# Single_stage.net
KiCad netlist of a schematic drawn in Altium Designer
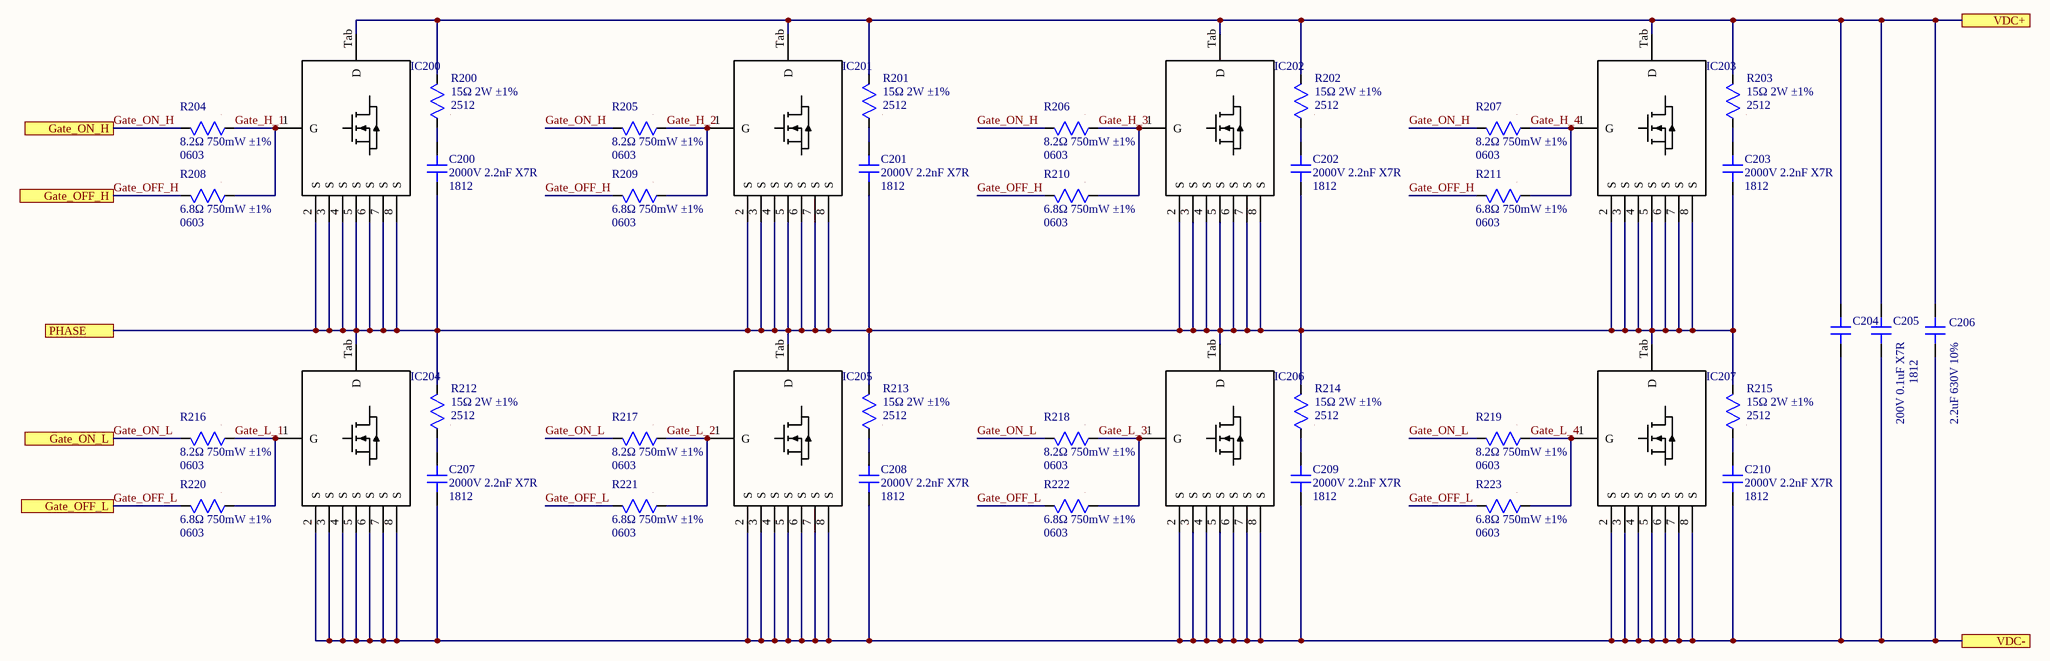
[diagram p0: Single_stage.SchDoc]

(export (version "E")
  (design (tool "Eeschema 10.0.6"))
  (components
    (comp (ref "C200")
      (value "2000V 2.2nF X7R")
      (footprint "CAP SMD 1812")
      (description "Condensadores de cerámica multicapa (MLCC- SMD/SMT) WCAP-CSMH 2000V 2200pF 1812 10%")
      (fields
        (field (name "PACKAGE") "1812")
        (field (name "MPN") "885342211007")
        (field (name "MANUFACTURER") "Wurth Elektronik")
      )
      (libsource (lib "eUSR_Database") (part "CAP non polarized"))
    )
    (comp (ref "C201")
      (value "2000V 2.2nF X7R")
      (footprint "CAP SMD 1812")
      (description "Condensadores de cerámica multicapa (MLCC- SMD/SMT) WCAP-CSMH 2000V 2200pF 1812 10%")
      (fields
        (field (name "PACKAGE") "1812")
        (field (name "MPN") "885342211007")
        (field (name "MANUFACTURER") "Wurth Elektronik")
      )
      (libsource (lib "eUSR_Database") (part "CAP non polarized"))
    )
    (comp (ref "C202")
      (value "2000V 2.2nF X7R")
      (footprint "CAP SMD 1812")
      (description "Condensadores de cerámica multicapa (MLCC- SMD/SMT) WCAP-CSMH 2000V 2200pF 1812 10%")
      (fields
        (field (name "PACKAGE") "1812")
        (field (name "MPN") "885342211007")
        (field (name "MANUFACTURER") "Wurth Elektronik")
      )
      (libsource (lib "eUSR_Database") (part "CAP non polarized"))
    )
    (comp (ref "C203")
      (value "2000V 2.2nF X7R")
      (footprint "CAP SMD 1812")
      (description "Condensadores de cerámica multicapa (MLCC- SMD/SMT) WCAP-CSMH 2000V 2200pF 1812 10%")
      (fields
        (field (name "PACKAGE") "1812")
        (field (name "MPN") "885342211007")
        (field (name "MANUFACTURER") "Wurth Elektronik")
      )
      (libsource (lib "eUSR_Database") (part "CAP non polarized"))
    )
    (comp (ref "C204")
      (value "CAP non polarized")
      (footprint "CAP SMD 1812")
      (description "Condensadores de cerámica multicapa (MLCC- SMD/SMT) WCAP-CSMH 200V 0.1uF 1812 10%")
      (fields (field (name "MPN") "885342211002") (field (name "MANUFACTURER") "Wurth Elektronik"))
      (libsource (lib "eUSR_Database") (part "CAP non polarized"))
    )
    (comp (ref "C205")
      (value "200V 0.1uF X7R")
      (footprint "CAP SMD 1812")
      (description "Condensadores de cerámica multicapa (MLCC- SMD/SMT) WCAP-CSMH 200V 0.1uF 1812 10%")
      (fields
        (field (name "PACKAGE") "1812")
        (field (name "MPN") "885342211002")
        (field (name "MANUFACTURER") "Wurth Elektronik")
      )
      (libsource (lib "eUSR_Database") (part "CAP non polarized"))
    )
    (comp (ref "C206")
      (value "2.2uF 630V 10%")
      (footprint "CAP_27.5Px30H")
      (description "Condensadores de película WCAP-FTXH 2.2 uF 10% 310V (AC)")
      (fields (field (name "MPN") "890414027011CS") (field (name "MANUFACTURER") "Wurth Elektronik"))
      (libsource (lib "eUSR_Database") (part "CAP non polarized"))
    )
    (comp (ref "C207")
      (value "2000V 2.2nF X7R")
      (footprint "CAP SMD 1812")
      (description "Condensadores de cerámica multicapa (MLCC- SMD/SMT) WCAP-CSMH 2000V 2200pF 1812 10%")
      (fields
        (field (name "PACKAGE") "1812")
        (field (name "MPN") "885342211007")
        (field (name "MANUFACTURER") "Wurth Elektronik")
      )
      (libsource (lib "eUSR_Database") (part "CAP non polarized"))
    )
    (comp (ref "C208")
      (value "2000V 2.2nF X7R")
      (footprint "CAP SMD 1812")
      (description "Condensadores de cerámica multicapa (MLCC- SMD/SMT) WCAP-CSMH 2000V 2200pF 1812 10%")
      (fields
        (field (name "PACKAGE") "1812")
        (field (name "MPN") "885342211007")
        (field (name "MANUFACTURER") "Wurth Elektronik")
      )
      (libsource (lib "eUSR_Database") (part "CAP non polarized"))
    )
    (comp (ref "C209")
      (value "2000V 2.2nF X7R")
      (footprint "CAP SMD 1812")
      (description "Condensadores de cerámica multicapa (MLCC- SMD/SMT) WCAP-CSMH 2000V 2200pF 1812 10%")
      (fields
        (field (name "PACKAGE") "1812")
        (field (name "MPN") "885342211007")
        (field (name "MANUFACTURER") "Wurth Elektronik")
      )
      (libsource (lib "eUSR_Database") (part "CAP non polarized"))
    )
    (comp (ref "C210")
      (value "2000V 2.2nF X7R")
      (footprint "CAP SMD 1812")
      (description "Condensadores de cerámica multicapa (MLCC- SMD/SMT) WCAP-CSMH 2000V 2200pF 1812 10%")
      (fields
        (field (name "PACKAGE") "1812")
        (field (name "MPN") "885342211007")
        (field (name "MANUFACTURER") "Wurth Elektronik")
      )
      (libsource (lib "eUSR_Database") (part "CAP non polarized"))
    )
    (comp (ref "IC200")
      (value "IAUTN15S6N025")
      (footprint "PG-HSOG-8-1")
      (description "MOSFET 150 V, N-Ch, 3.8 mOhms max, Automotive MOSFET, TOLT (10x15)")
      (fields
        (field (name "MPN") "IAUTN15S6N025GATMA1")
        (field (name "MANUFACTURER") "Infineon Technologies")
      )
      (libsource (lib "eUSR_Database") (part "IAUTN15S6N025"))
    )
    (comp (ref "IC201")
      (value "IAUTN15S6N025")
      (footprint "PG-HSOG-8-1")
      (description "MOSFET 150 V, N-Ch, 3.8 mOhms max, Automotive MOSFET, TOLT (10x15)")
      (fields
        (field (name "MPN") "IAUTN15S6N025GATMA1")
        (field (name "MANUFACTURER") "Infineon Technologies")
      )
      (libsource (lib "eUSR_Database") (part "IAUTN15S6N025"))
    )
    (comp (ref "IC202")
      (value "IAUTN15S6N025")
      (footprint "PG-HSOG-8-1")
      (description "MOSFET 150 V, N-Ch, 3.8 mOhms max, Automotive MOSFET, TOLT (10x15)")
      (fields
        (field (name "MPN") "IAUTN15S6N025GATMA1")
        (field (name "MANUFACTURER") "Infineon Technologies")
      )
      (libsource (lib "eUSR_Database") (part "IAUTN15S6N025"))
    )
    (comp (ref "IC203")
      (value "IAUTN15S6N025")
      (footprint "PG-HSOG-8-1")
      (description "MOSFET 150 V, N-Ch, 3.8 mOhms max, Automotive MOSFET, TOLT (10x15)")
      (fields
        (field (name "MPN") "IAUTN15S6N025GATMA1")
        (field (name "MANUFACTURER") "Infineon Technologies")
      )
      (libsource (lib "eUSR_Database") (part "IAUTN15S6N025"))
    )
    (comp (ref "IC204")
      (value "IAUTN15S6N025")
      (footprint "PG-HSOG-8-1")
      (description "MOSFET 150 V, N-Ch, 3.8 mOhms max, Automotive MOSFET, TOLT (10x15)")
      (fields
        (field (name "MPN") "IAUTN15S6N025GATMA1")
        (field (name "MANUFACTURER") "Infineon Technologies")
      )
      (libsource (lib "eUSR_Database") (part "IAUTN15S6N025"))
    )
    (comp (ref "IC205")
      (value "IAUTN15S6N025")
      (footprint "PG-HSOG-8-1")
      (description "MOSFET 150 V, N-Ch, 3.8 mOhms max, Automotive MOSFET, TOLT (10x15)")
      (fields
        (field (name "MPN") "IAUTN15S6N025GATMA1")
        (field (name "MANUFACTURER") "Infineon Technologies")
      )
      (libsource (lib "eUSR_Database") (part "IAUTN15S6N025"))
    )
    (comp (ref "IC206")
      (value "IAUTN15S6N025")
      (footprint "PG-HSOG-8-1")
      (description "MOSFET 150 V, N-Ch, 3.8 mOhms max, Automotive MOSFET, TOLT (10x15)")
      (fields
        (field (name "MPN") "IAUTN15S6N025GATMA1")
        (field (name "MANUFACTURER") "Infineon Technologies")
      )
      (libsource (lib "eUSR_Database") (part "IAUTN15S6N025"))
    )
    (comp (ref "IC207")
      (value "IAUTN15S6N025")
      (footprint "PG-HSOG-8-1")
      (description "MOSFET 150 V, N-Ch, 3.8 mOhms max, Automotive MOSFET, TOLT (10x15)")
      (fields
        (field (name "MPN") "IAUTN15S6N025GATMA1")
        (field (name "MANUFACTURER") "Infineon Technologies")
      )
      (libsource (lib "eUSR_Database") (part "IAUTN15S6N025"))
    )
    (comp (ref "R200")
      (value "15Ω 2W ±1%")
      (footprint "RES SMD 2512")
      (description "Resistores de película gruesa - SMD CRGP 2512 15R 1% SMD Resistor")
      (fields
        (field (name "PACKAGE") "2512")
        (field (name "MPN") "CRGP2512F15R")
        (field (name "MANUFACTURER") "TE Connectivity / Holsworthy")
      )
      (libsource (lib "eUSR_Database") (part "RES"))
    )
    (comp (ref "R201")
      (value "15Ω 2W ±1%")
      (footprint "RES SMD 2512")
      (description "Resistores de película gruesa - SMD CRGP 2512 15R 1% SMD Resistor")
      (fields
        (field (name "PACKAGE") "2512")
        (field (name "MPN") "CRGP2512F15R")
        (field (name "MANUFACTURER") "TE Connectivity / Holsworthy")
      )
      (libsource (lib "eUSR_Database") (part "RES"))
    )
    (comp (ref "R202")
      (value "15Ω 2W ±1%")
      (footprint "RES SMD 2512")
      (description "Resistores de película gruesa - SMD CRGP 2512 15R 1% SMD Resistor")
      (fields
        (field (name "PACKAGE") "2512")
        (field (name "MPN") "CRGP2512F15R")
        (field (name "MANUFACTURER") "TE Connectivity / Holsworthy")
      )
      (libsource (lib "eUSR_Database") (part "RES"))
    )
    (comp (ref "R203")
      (value "15Ω 2W ±1%")
      (footprint "RES SMD 2512")
      (description "Resistores de película gruesa - SMD CRGP 2512 15R 1% SMD Resistor")
      (fields
        (field (name "PACKAGE") "2512")
        (field (name "MPN") "CRGP2512F15R")
        (field (name "MANUFACTURER") "TE Connectivity / Holsworthy")
      )
      (libsource (lib "eUSR_Database") (part "RES"))
    )
    (comp (ref "R204")
      (value "8.2Ω 750mW ±1%")
      (footprint "RES SMD 0603")
      (description "Resistores de película gruesa - SMD 0.75W 8.2ohms 1% High Power AEC-Q200")
      (fields
        (field (name "PACKAGE") "0603")
        (field (name "MPN") "CRCW06038R20FKEAHP")
        (field (name "MANUFACTURER") "Vishay Intertech")
      )
      (libsource (lib "eUSR_Database") (part "RES"))
    )
    (comp (ref "R205")
      (value "8.2Ω 750mW ±1%")
      (footprint "RES SMD 0603")
      (description "Resistores de película gruesa - SMD 0.75W 8.2ohms 1% High Power AEC-Q200")
      (fields
        (field (name "PACKAGE") "0603")
        (field (name "MPN") "CRCW06038R20FKEAHP")
        (field (name "MANUFACTURER") "Vishay Intertech")
      )
      (libsource (lib "eUSR_Database") (part "RES"))
    )
    (comp (ref "R206")
      (value "8.2Ω 750mW ±1%")
      (footprint "RES SMD 0603")
      (description "Resistores de película gruesa - SMD 0.75W 8.2ohms 1% High Power AEC-Q200")
      (fields
        (field (name "PACKAGE") "0603")
        (field (name "MPN") "CRCW06038R20FKEAHP")
        (field (name "MANUFACTURER") "Vishay Intertech")
      )
      (libsource (lib "eUSR_Database") (part "RES"))
    )
    (comp (ref "R207")
      (value "8.2Ω 750mW ±1%")
      (footprint "RES SMD 0603")
      (description "Resistores de película gruesa - SMD 0.75W 8.2ohms 1% High Power AEC-Q200")
      (fields
        (field (name "PACKAGE") "0603")
        (field (name "MPN") "CRCW06038R20FKEAHP")
        (field (name "MANUFACTURER") "Vishay Intertech")
      )
      (libsource (lib "eUSR_Database") (part "RES"))
    )
    (comp (ref "R208")
      (value "6.8Ω 750mW ±1%")
      (footprint "RES SMD 0603")
      (description "Resistores de película gruesa - SMD 0.75W 6.8ohms 1% High Power AEC-Q200")
      (fields
        (field (name "PACKAGE") "0603")
        (field (name "MPN") "CRCW06036R80FKEAHP")
        (field (name "MANUFACTURER") "Vishay Intertech")
      )
      (libsource (lib "eUSR_Database") (part "RES"))
    )
    (comp (ref "R209")
      (value "6.8Ω 750mW ±1%")
      (footprint "RES SMD 0603")
      (description "Resistores de película gruesa - SMD 0.75W 6.8ohms 1% High Power AEC-Q200")
      (fields
        (field (name "PACKAGE") "0603")
        (field (name "MPN") "CRCW06036R80FKEAHP")
        (field (name "MANUFACTURER") "Vishay Intertech")
      )
      (libsource (lib "eUSR_Database") (part "RES"))
    )
    (comp (ref "R210")
      (value "6.8Ω 750mW ±1%")
      (footprint "RES SMD 0603")
      (description "Resistores de película gruesa - SMD 0.75W 6.8ohms 1% High Power AEC-Q200")
      (fields
        (field (name "PACKAGE") "0603")
        (field (name "MPN") "CRCW06036R80FKEAHP")
        (field (name "MANUFACTURER") "Vishay Intertech")
      )
      (libsource (lib "eUSR_Database") (part "RES"))
    )
    (comp (ref "R211")
      (value "6.8Ω 750mW ±1%")
      (footprint "RES SMD 0603")
      (description "Resistores de película gruesa - SMD 0.75W 6.8ohms 1% High Power AEC-Q200")
      (fields
        (field (name "PACKAGE") "0603")
        (field (name "MPN") "CRCW06036R80FKEAHP")
        (field (name "MANUFACTURER") "Vishay Intertech")
      )
      (libsource (lib "eUSR_Database") (part "RES"))
    )
    (comp (ref "R212")
      (value "15Ω 2W ±1%")
      (footprint "RES SMD 2512")
      (description "Resistores de película gruesa - SMD CRGP 2512 15R 1% SMD Resistor")
      (fields
        (field (name "PACKAGE") "2512")
        (field (name "MPN") "CRGP2512F15R")
        (field (name "MANUFACTURER") "TE Connectivity / Holsworthy")
      )
      (libsource (lib "eUSR_Database") (part "RES"))
    )
    (comp (ref "R213")
      (value "15Ω 2W ±1%")
      (footprint "RES SMD 2512")
      (description "Resistores de película gruesa - SMD CRGP 2512 15R 1% SMD Resistor")
      (fields
        (field (name "PACKAGE") "2512")
        (field (name "MPN") "CRGP2512F15R")
        (field (name "MANUFACTURER") "TE Connectivity / Holsworthy")
      )
      (libsource (lib "eUSR_Database") (part "RES"))
    )
    (comp (ref "R214")
      (value "15Ω 2W ±1%")
      (footprint "RES SMD 2512")
      (description "Resistores de película gruesa - SMD CRGP 2512 15R 1% SMD Resistor")
      (fields
        (field (name "PACKAGE") "2512")
        (field (name "MPN") "CRGP2512F15R")
        (field (name "MANUFACTURER") "TE Connectivity / Holsworthy")
      )
      (libsource (lib "eUSR_Database") (part "RES"))
    )
    (comp (ref "R215")
      (value "15Ω 2W ±1%")
      (footprint "RES SMD 2512")
      (description "Resistores de película gruesa - SMD CRGP 2512 15R 1% SMD Resistor")
      (fields
        (field (name "PACKAGE") "2512")
        (field (name "MPN") "CRGP2512F15R")
        (field (name "MANUFACTURER") "TE Connectivity / Holsworthy")
      )
      (libsource (lib "eUSR_Database") (part "RES"))
    )
    (comp (ref "R216")
      (value "8.2Ω 750mW ±1%")
      (footprint "RES SMD 0603")
      (description "Resistores de película gruesa - SMD 0.75W 8.2ohms 1% High Power AEC-Q200")
      (fields
        (field (name "PACKAGE") "0603")
        (field (name "MPN") "CRCW06038R20FKEAHP")
        (field (name "MANUFACTURER") "Vishay Intertech")
      )
      (libsource (lib "eUSR_Database") (part "RES"))
    )
    (comp (ref "R217")
      (value "8.2Ω 750mW ±1%")
      (footprint "RES SMD 0603")
      (description "Resistores de película gruesa - SMD 0.75W 8.2ohms 1% High Power AEC-Q200")
      (fields
        (field (name "PACKAGE") "0603")
        (field (name "MPN") "CRCW06038R20FKEAHP")
        (field (name "MANUFACTURER") "Vishay Intertech")
      )
      (libsource (lib "eUSR_Database") (part "RES"))
    )
    (comp (ref "R218")
      (value "8.2Ω 750mW ±1%")
      (footprint "RES SMD 0603")
      (description "Resistores de película gruesa - SMD 0.75W 8.2ohms 1% High Power AEC-Q200")
      (fields
        (field (name "PACKAGE") "0603")
        (field (name "MPN") "CRCW06038R20FKEAHP")
        (field (name "MANUFACTURER") "Vishay Intertech")
      )
      (libsource (lib "eUSR_Database") (part "RES"))
    )
    (comp (ref "R219")
      (value "8.2Ω 750mW ±1%")
      (footprint "RES SMD 0603")
      (description "Resistores de película gruesa - SMD 0.75W 8.2ohms 1% High Power AEC-Q200")
      (fields
        (field (name "PACKAGE") "0603")
        (field (name "MPN") "CRCW06038R20FKEAHP")
        (field (name "MANUFACTURER") "Vishay Intertech")
      )
      (libsource (lib "eUSR_Database") (part "RES"))
    )
    (comp (ref "R220")
      (value "6.8Ω 750mW ±1%")
      (footprint "RES SMD 0603")
      (description "Resistores de película gruesa - SMD 0.75W 6.8ohms 1% High Power AEC-Q200")
      (fields
        (field (name "PACKAGE") "0603")
        (field (name "MPN") "CRCW06036R80FKEAHP")
        (field (name "MANUFACTURER") "Vishay Intertech")
      )
      (libsource (lib "eUSR_Database") (part "RES"))
    )
    (comp (ref "R221")
      (value "6.8Ω 750mW ±1%")
      (footprint "RES SMD 0603")
      (description "Resistores de película gruesa - SMD 0.75W 6.8ohms 1% High Power AEC-Q200")
      (fields
        (field (name "PACKAGE") "0603")
        (field (name "MPN") "CRCW06036R80FKEAHP")
        (field (name "MANUFACTURER") "Vishay Intertech")
      )
      (libsource (lib "eUSR_Database") (part "RES"))
    )
    (comp (ref "R222")
      (value "6.8Ω 750mW ±1%")
      (footprint "RES SMD 0603")
      (description "Resistores de película gruesa - SMD 0.75W 6.8ohms 1% High Power AEC-Q200")
      (fields
        (field (name "PACKAGE") "0603")
        (field (name "MPN") "CRCW06036R80FKEAHP")
        (field (name "MANUFACTURER") "Vishay Intertech")
      )
      (libsource (lib "eUSR_Database") (part "RES"))
    )
    (comp (ref "R223")
      (value "6.8Ω 750mW ±1%")
      (footprint "RES SMD 0603")
      (description "Resistores de película gruesa - SMD 0.75W 6.8ohms 1% High Power AEC-Q200")
      (fields
        (field (name "PACKAGE") "0603")
        (field (name "MPN") "CRCW06036R80FKEAHP")
        (field (name "MANUFACTURER") "Vishay Intertech")
      )
      (libsource (lib "eUSR_Database") (part "RES"))
    )
  )
  (nets
    (net (code "1") (name "/Gate_H_1") (class "Default")
      (node (ref "IC200") (pin "1") (pinfunction "G_1") (pintype "passive"))
      (node (ref "R204") (pin "1") (pinfunction "1_1") (pintype "passive"))
      (node (ref "R208") (pin "1") (pinfunction "1_1") (pintype "passive"))
    )
    (net (code "2") (name "/Gate_H_2") (class "Default")
      (node (ref "IC201") (pin "1") (pinfunction "G_1") (pintype "passive"))
      (node (ref "R205") (pin "1") (pinfunction "1_1") (pintype "passive"))
      (node (ref "R209") (pin "1") (pinfunction "1_1") (pintype "passive"))
    )
    (net (code "3") (name "/Gate_H_3") (class "Default")
      (node (ref "IC202") (pin "1") (pinfunction "G_1") (pintype "passive"))
      (node (ref "R206") (pin "1") (pinfunction "1_1") (pintype "passive"))
      (node (ref "R210") (pin "1") (pinfunction "1_1") (pintype "passive"))
    )
    (net (code "4") (name "/Gate_H_4") (class "Default")
      (node (ref "IC203") (pin "1") (pinfunction "G_1") (pintype "passive"))
      (node (ref "R207") (pin "1") (pinfunction "1_1") (pintype "passive"))
      (node (ref "R211") (pin "1") (pinfunction "1_1") (pintype "passive"))
    )
    (net (code "5") (name "/Gate_L_1") (class "Default")
      (node (ref "IC204") (pin "1") (pinfunction "G_1") (pintype "passive"))
      (node (ref "R216") (pin "1") (pinfunction "1_1") (pintype "passive"))
      (node (ref "R220") (pin "1") (pinfunction "1_1") (pintype "passive"))
    )
    (net (code "6") (name "/Gate_L_2") (class "Default")
      (node (ref "IC205") (pin "1") (pinfunction "G_1") (pintype "passive"))
      (node (ref "R217") (pin "1") (pinfunction "1_1") (pintype "passive"))
      (node (ref "R221") (pin "1") (pinfunction "1_1") (pintype "passive"))
    )
    (net (code "7") (name "/Gate_L_3") (class "Default")
      (node (ref "IC206") (pin "1") (pinfunction "G_1") (pintype "passive"))
      (node (ref "R218") (pin "1") (pinfunction "1_1") (pintype "passive"))
      (node (ref "R222") (pin "1") (pinfunction "1_1") (pintype "passive"))
    )
    (net (code "8") (name "/Gate_L_4") (class "Default")
      (node (ref "IC207") (pin "1") (pinfunction "G_1") (pintype "passive"))
      (node (ref "R219") (pin "1") (pinfunction "1_1") (pintype "passive"))
      (node (ref "R223") (pin "1") (pinfunction "1_1") (pintype "passive"))
    )
    (net (code "9") (name "/Gate_OFF_H") (class "Default")
      (node (ref "R208") (pin "2") (pinfunction "2_2") (pintype "passive"))
      (node (ref "R209") (pin "2") (pinfunction "2_2") (pintype "passive"))
      (node (ref "R210") (pin "2") (pinfunction "2_2") (pintype "passive"))
      (node (ref "R211") (pin "2") (pinfunction "2_2") (pintype "passive"))
    )
    (net (code "10") (name "/Gate_OFF_L") (class "Default")
      (node (ref "R220") (pin "2") (pinfunction "2_2") (pintype "passive"))
      (node (ref "R221") (pin "2") (pinfunction "2_2") (pintype "passive"))
      (node (ref "R222") (pin "2") (pinfunction "2_2") (pintype "passive"))
      (node (ref "R223") (pin "2") (pinfunction "2_2") (pintype "passive"))
    )
    (net (code "11") (name "/Gate_ON_H") (class "Default")
      (node (ref "R204") (pin "2") (pinfunction "2_2") (pintype "passive"))
      (node (ref "R205") (pin "2") (pinfunction "2_2") (pintype "passive"))
      (node (ref "R206") (pin "2") (pinfunction "2_2") (pintype "passive"))
      (node (ref "R207") (pin "2") (pinfunction "2_2") (pintype "passive"))
    )
    (net (code "12") (name "/Gate_ON_L") (class "Default")
      (node (ref "R216") (pin "2") (pinfunction "2_2") (pintype "passive"))
      (node (ref "R217") (pin "2") (pinfunction "2_2") (pintype "passive"))
      (node (ref "R218") (pin "2") (pinfunction "2_2") (pintype "passive"))
      (node (ref "R219") (pin "2") (pinfunction "2_2") (pintype "passive"))
    )
    (net (code "13") (name "/PHASE") (class "Default")
      (node (ref "C200") (pin "2") (pinfunction "2_2") (pintype "passive"))
      (node (ref "C201") (pin "2") (pinfunction "2_2") (pintype "passive"))
      (node (ref "C202") (pin "2") (pinfunction "2_2") (pintype "passive"))
      (node (ref "C203") (pin "2") (pinfunction "2_2") (pintype "passive"))
      (node (ref "IC200") (pin "2") (pinfunction "S_2") (pintype "power_in"))
      (node (ref "IC200") (pin "3") (pinfunction "S_3") (pintype "power_in"))
      (node (ref "IC200") (pin "4") (pinfunction "S_4") (pintype "power_in"))
      (node (ref "IC200") (pin "5") (pinfunction "S_5") (pintype "power_in"))
      (node (ref "IC200") (pin "6") (pinfunction "S_6") (pintype "power_in"))
      (node (ref "IC200") (pin "7") (pinfunction "S_7") (pintype "power_in"))
      (node (ref "IC200") (pin "8") (pinfunction "S_8") (pintype "power_in"))
      (node (ref "IC201") (pin "2") (pinfunction "S_2") (pintype "power_in"))
      (node (ref "IC201") (pin "3") (pinfunction "S_3") (pintype "power_in"))
      (node (ref "IC201") (pin "4") (pinfunction "S_4") (pintype "power_in"))
      (node (ref "IC201") (pin "5") (pinfunction "S_5") (pintype "power_in"))
      (node (ref "IC201") (pin "6") (pinfunction "S_6") (pintype "power_in"))
      (node (ref "IC201") (pin "7") (pinfunction "S_7") (pintype "power_in"))
      (node (ref "IC201") (pin "8") (pinfunction "S_8") (pintype "power_in"))
      (node (ref "IC202") (pin "2") (pinfunction "S_2") (pintype "power_in"))
      (node (ref "IC202") (pin "3") (pinfunction "S_3") (pintype "power_in"))
      (node (ref "IC202") (pin "4") (pinfunction "S_4") (pintype "power_in"))
      (node (ref "IC202") (pin "5") (pinfunction "S_5") (pintype "power_in"))
      (node (ref "IC202") (pin "6") (pinfunction "S_6") (pintype "power_in"))
      (node (ref "IC202") (pin "7") (pinfunction "S_7") (pintype "power_in"))
      (node (ref "IC202") (pin "8") (pinfunction "S_8") (pintype "power_in"))
      (node (ref "IC203") (pin "2") (pinfunction "S_2") (pintype "power_in"))
      (node (ref "IC203") (pin "3") (pinfunction "S_3") (pintype "power_in"))
      (node (ref "IC203") (pin "4") (pinfunction "S_4") (pintype "power_in"))
      (node (ref "IC203") (pin "5") (pinfunction "S_5") (pintype "power_in"))
      (node (ref "IC203") (pin "6") (pinfunction "S_6") (pintype "power_in"))
      (node (ref "IC203") (pin "7") (pinfunction "S_7") (pintype "power_in"))
      (node (ref "IC203") (pin "8") (pinfunction "S_8") (pintype "power_in"))
      (node (ref "IC204") (pin "Tab") (pinfunction "D_Tab") (pintype "power_in"))
      (node (ref "IC205") (pin "Tab") (pinfunction "D_Tab") (pintype "power_in"))
      (node (ref "IC206") (pin "Tab") (pinfunction "D_Tab") (pintype "power_in"))
      (node (ref "IC207") (pin "Tab") (pinfunction "D_Tab") (pintype "power_in"))
      (node (ref "R212") (pin "2") (pinfunction "2_2") (pintype "passive"))
      (node (ref "R213") (pin "2") (pinfunction "2_2") (pintype "passive"))
      (node (ref "R214") (pin "2") (pinfunction "2_2") (pintype "passive"))
      (node (ref "R215") (pin "2") (pinfunction "2_2") (pintype "passive"))
    )
    (net (code "14") (name "/VDC+") (class "Default")
      (node (ref "C204") (pin "1") (pinfunction "1_1") (pintype "passive"))
      (node (ref "C205") (pin "1") (pinfunction "1_1") (pintype "passive"))
      (node (ref "C206") (pin "1") (pinfunction "1_1") (pintype "passive"))
      (node (ref "IC200") (pin "Tab") (pinfunction "D_Tab") (pintype "power_in"))
      (node (ref "IC201") (pin "Tab") (pinfunction "D_Tab") (pintype "power_in"))
      (node (ref "IC202") (pin "Tab") (pinfunction "D_Tab") (pintype "power_in"))
      (node (ref "IC203") (pin "Tab") (pinfunction "D_Tab") (pintype "power_in"))
      (node (ref "R200") (pin "2") (pinfunction "2_2") (pintype "passive"))
      (node (ref "R201") (pin "2") (pinfunction "2_2") (pintype "passive"))
      (node (ref "R202") (pin "2") (pinfunction "2_2") (pintype "passive"))
      (node (ref "R203") (pin "2") (pinfunction "2_2") (pintype "passive"))
    )
    (net (code "15") (name "/VDC-") (class "Default")
      (node (ref "C204") (pin "2") (pinfunction "2_2") (pintype "passive"))
      (node (ref "C205") (pin "2") (pinfunction "2_2") (pintype "passive"))
      (node (ref "C206") (pin "2") (pinfunction "2_2") (pintype "passive"))
      (node (ref "C207") (pin "2") (pinfunction "2_2") (pintype "passive"))
      (node (ref "C208") (pin "2") (pinfunction "2_2") (pintype "passive"))
      (node (ref "C209") (pin "2") (pinfunction "2_2") (pintype "passive"))
      (node (ref "C210") (pin "2") (pinfunction "2_2") (pintype "passive"))
      (node (ref "IC204") (pin "2") (pinfunction "S_2") (pintype "power_in"))
      (node (ref "IC204") (pin "3") (pinfunction "S_3") (pintype "power_in"))
      (node (ref "IC204") (pin "4") (pinfunction "S_4") (pintype "power_in"))
      (node (ref "IC204") (pin "5") (pinfunction "S_5") (pintype "power_in"))
      (node (ref "IC204") (pin "6") (pinfunction "S_6") (pintype "power_in"))
      (node (ref "IC204") (pin "7") (pinfunction "S_7") (pintype "power_in"))
      (node (ref "IC204") (pin "8") (pinfunction "S_8") (pintype "power_in"))
      (node (ref "IC205") (pin "2") (pinfunction "S_2") (pintype "power_in"))
      (node (ref "IC205") (pin "3") (pinfunction "S_3") (pintype "power_in"))
      (node (ref "IC205") (pin "4") (pinfunction "S_4") (pintype "power_in"))
      (node (ref "IC205") (pin "5") (pinfunction "S_5") (pintype "power_in"))
      (node (ref "IC205") (pin "6") (pinfunction "S_6") (pintype "power_in"))
      (node (ref "IC205") (pin "7") (pinfunction "S_7") (pintype "power_in"))
      (node (ref "IC205") (pin "8") (pinfunction "S_8") (pintype "power_in"))
      (node (ref "IC206") (pin "2") (pinfunction "S_2") (pintype "power_in"))
      (node (ref "IC206") (pin "3") (pinfunction "S_3") (pintype "power_in"))
      (node (ref "IC206") (pin "4") (pinfunction "S_4") (pintype "power_in"))
      (node (ref "IC206") (pin "5") (pinfunction "S_5") (pintype "power_in"))
      (node (ref "IC206") (pin "6") (pinfunction "S_6") (pintype "power_in"))
      (node (ref "IC206") (pin "7") (pinfunction "S_7") (pintype "power_in"))
      (node (ref "IC206") (pin "8") (pinfunction "S_8") (pintype "power_in"))
      (node (ref "IC207") (pin "2") (pinfunction "S_2") (pintype "power_in"))
      (node (ref "IC207") (pin "3") (pinfunction "S_3") (pintype "power_in"))
      (node (ref "IC207") (pin "4") (pinfunction "S_4") (pintype "power_in"))
      (node (ref "IC207") (pin "5") (pinfunction "S_5") (pintype "power_in"))
      (node (ref "IC207") (pin "6") (pinfunction "S_6") (pintype "power_in"))
      (node (ref "IC207") (pin "7") (pinfunction "S_7") (pintype "power_in"))
      (node (ref "IC207") (pin "8") (pinfunction "S_8") (pintype "power_in"))
    )
    (net (code "16") (name "Net-(C200-Pad1)") (class "Default")
      (node (ref "C200") (pin "1") (pinfunction "1_1") (pintype "passive"))
      (node (ref "R200") (pin "1") (pinfunction "1_1") (pintype "passive"))
    )
    (net (code "17") (name "Net-(C201-Pad1)") (class "Default")
      (node (ref "C201") (pin "1") (pinfunction "1_1") (pintype "passive"))
      (node (ref "R201") (pin "1") (pinfunction "1_1") (pintype "passive"))
    )
    (net (code "18") (name "Net-(C202-Pad1)") (class "Default")
      (node (ref "C202") (pin "1") (pinfunction "1_1") (pintype "passive"))
      (node (ref "R202") (pin "1") (pinfunction "1_1") (pintype "passive"))
    )
    (net (code "19") (name "Net-(C203-Pad1)") (class "Default")
      (node (ref "C203") (pin "1") (pinfunction "1_1") (pintype "passive"))
      (node (ref "R203") (pin "1") (pinfunction "1_1") (pintype "passive"))
    )
    (net (code "20") (name "Net-(C207-Pad1)") (class "Default")
      (node (ref "C207") (pin "1") (pinfunction "1_1") (pintype "passive"))
      (node (ref "R212") (pin "1") (pinfunction "1_1") (pintype "passive"))
    )
    (net (code "21") (name "Net-(C208-Pad1)") (class "Default")
      (node (ref "C208") (pin "1") (pinfunction "1_1") (pintype "passive"))
      (node (ref "R213") (pin "1") (pinfunction "1_1") (pintype "passive"))
    )
    (net (code "22") (name "Net-(C209-Pad1)") (class "Default")
      (node (ref "C209") (pin "1") (pinfunction "1_1") (pintype "passive"))
      (node (ref "R214") (pin "1") (pinfunction "1_1") (pintype "passive"))
    )
    (net (code "23") (name "Net-(C210-Pad1)") (class "Default")
      (node (ref "C210") (pin "1") (pinfunction "1_1") (pintype "passive"))
      (node (ref "R215") (pin "1") (pinfunction "1_1") (pintype "passive"))
    )
  )
)
